# Sheet1.net
KiCad netlist of a schematic drawn in Altium Designer
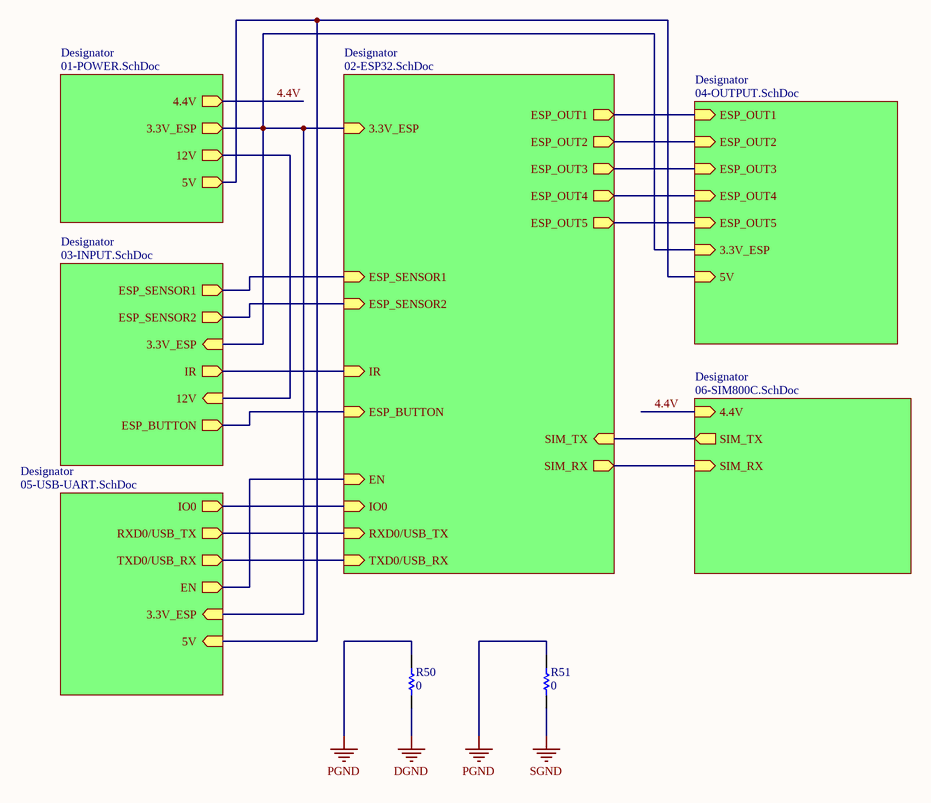
[diagram p0: Sheet1.SchDoc]

(export (version "E")
  (design (tool "Eeschema 10.0.6"))
  (components
    (comp (ref "R50")
      (value "0")
      (footprint "RESC2012(0805)")
      (description "0 Ohms ±1% 0.125W, 1/8W Chip Resistor 0805 (2012 Metric) Automotive AEC-Q200 Thick Film")
      (libsource (lib "GSHT_181013") (part "34.8K/R0805/1%"))
    )
    (comp (ref "R51")
      (value "0")
      (footprint "RESC2012(0805)")
      (description "0 Ohms ±1% 0.125W, 1/8W Chip Resistor 0805 (2012 Metric) Automotive AEC-Q200 Thick Film")
      (libsource (lib "GSHT_181013") (part "34.8K/R0805/1%"))
    )
  )
  (nets
    (net (code "20") (name "DGND") (class "Default")
      (node (ref "R50") (pin "2") (pinfunction "2_2") (pintype "passive"))
    )
    (net (code "21") (name "PGND") (class "Default")
      (node (ref "R50") (pin "1") (pinfunction "1_1") (pintype "passive"))
      (node (ref "R51") (pin "1") (pinfunction "1_1") (pintype "passive"))
    )
    (net (code "22") (name "SGND") (class "Default")
      (node (ref "R51") (pin "2") (pinfunction "2_2") (pintype "passive"))
    )
  )
)
